# Double_H_Bridge_v1_0.net
KiCad netlist of a schematic drawn in Altium Designer
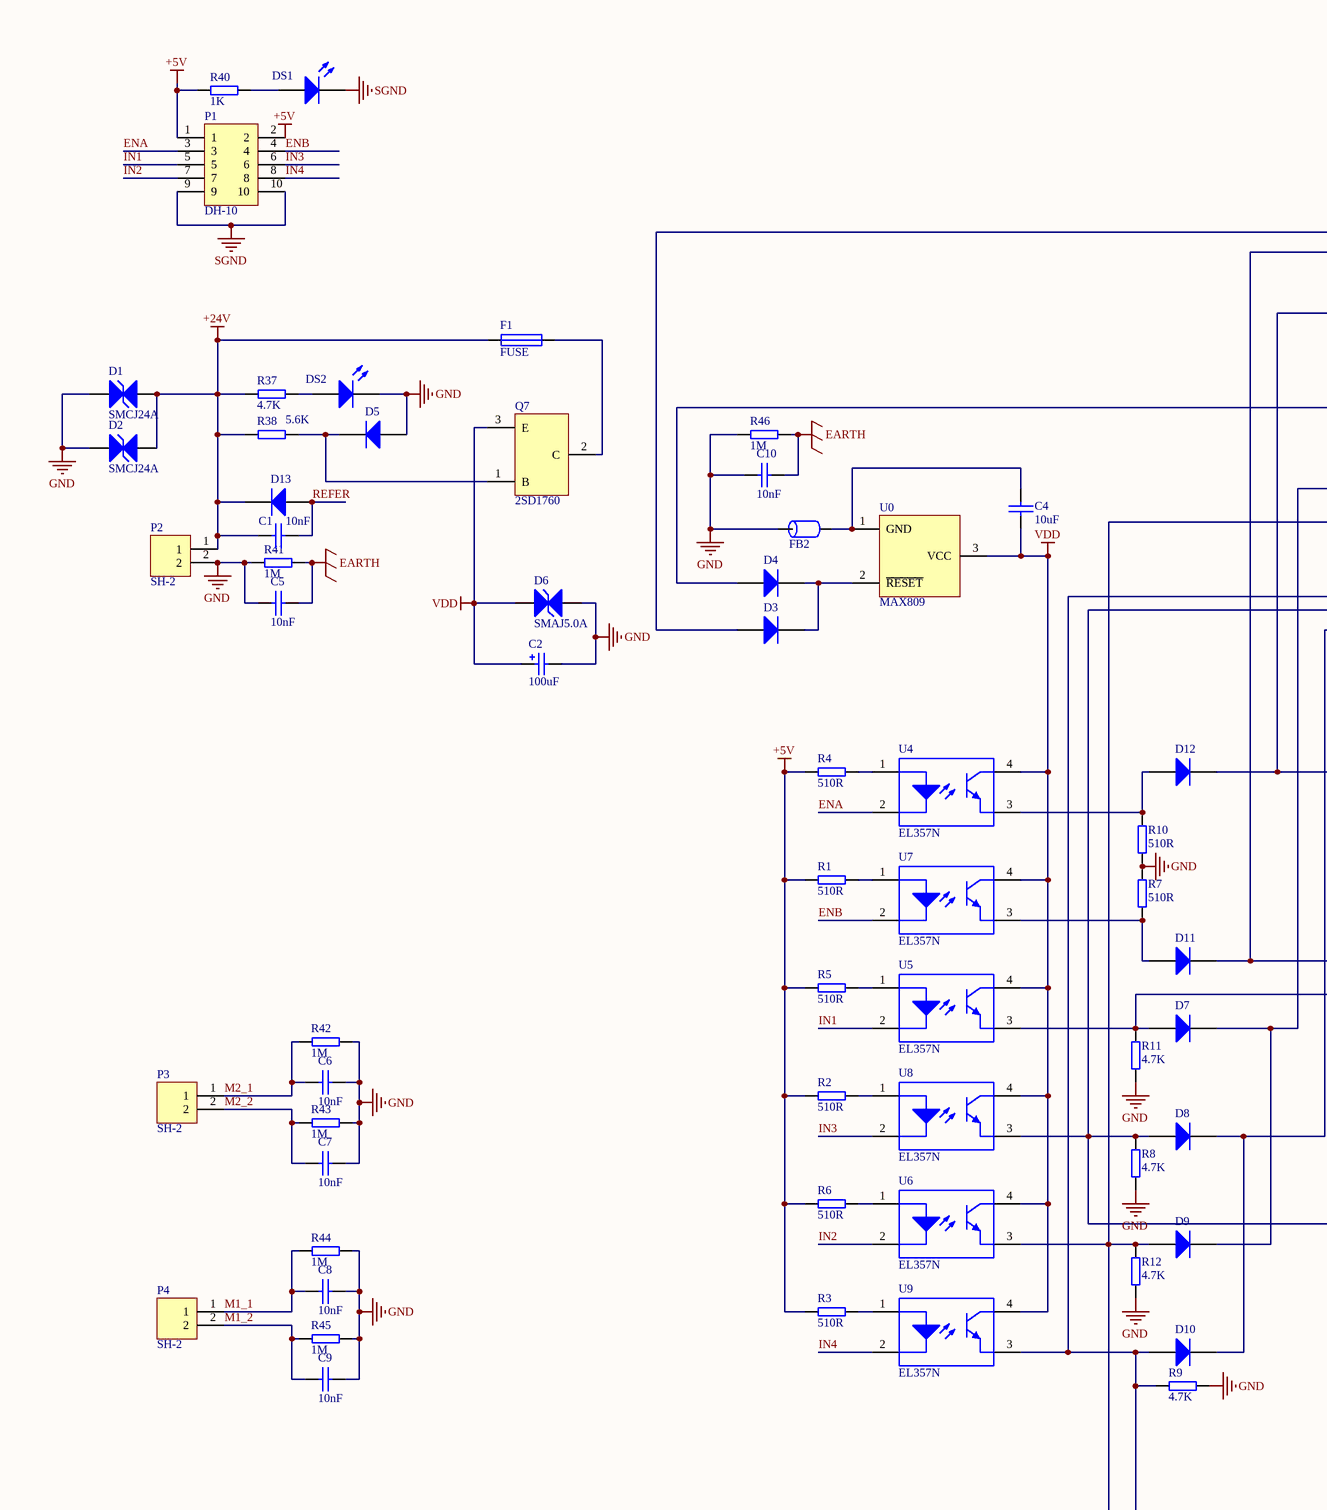
[diagram p0: Double_H_Bridge_v1.0.SchDoc, left]
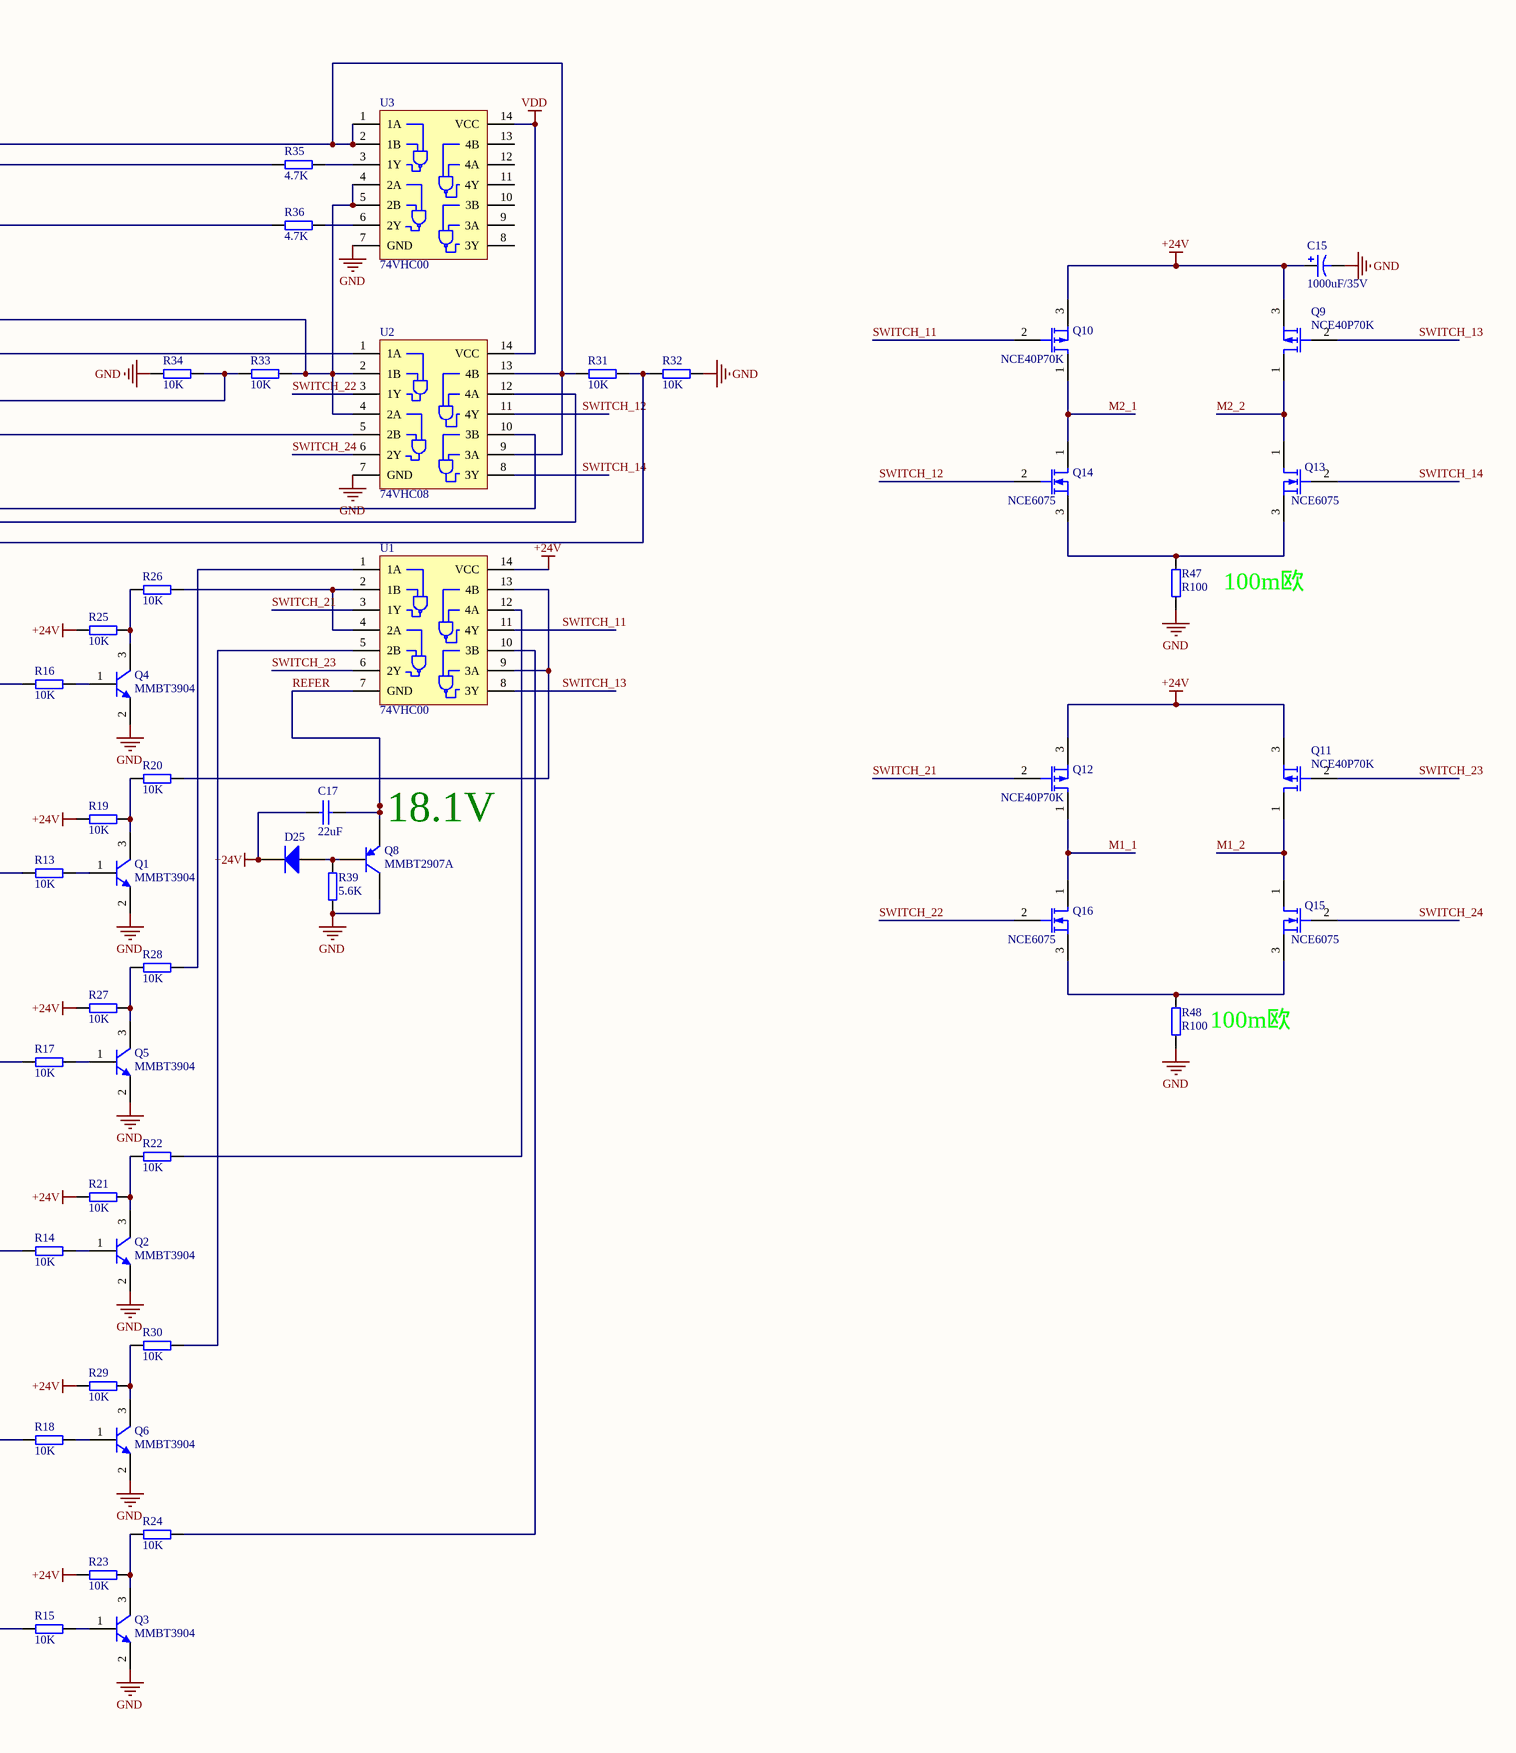
[diagram p1: Double_H_Bridge_v1.0.SchDoc, right]

(export (version "E")
  (design (tool "Eeschema 10.0.6"))
  (components
    (comp (ref "C1")
      (value "10nF")
      (footprint "0603")
      (description "电容")
      (libsource (lib "Component") (part "CAP"))
    )
    (comp (ref "C2") (value "100uF") (footprint "CA6032-C") (libsource (lib "Componet") (part "CapAEC*4")))
    (comp (ref "C4")
      (value "10uF")
      (footprint "0805")
      (description "电容")
      (libsource (lib "Component") (part "CAP"))
    )
    (comp (ref "C5")
      (value "10nF")
      (footprint "0603")
      (description "电容")
      (libsource (lib "Component") (part "CAP"))
    )
    (comp (ref "C6")
      (value "10nF")
      (footprint "0603")
      (description "电容")
      (libsource (lib "Component") (part "CAP"))
    )
    (comp (ref "C7")
      (value "10nF")
      (footprint "0603")
      (description "电容")
      (libsource (lib "Component") (part "CAP"))
    )
    (comp (ref "C8")
      (value "10nF")
      (footprint "0603")
      (description "电容")
      (libsource (lib "Component") (part "CAP"))
    )
    (comp (ref "C9")
      (value "10nF")
      (footprint "0603")
      (description "电容")
      (libsource (lib "Component") (part "CAP"))
    )
    (comp (ref "C10")
      (value "10nF")
      (footprint "0603")
      (description "电容")
      (libsource (lib "Component") (part "CAP"))
    )
    (comp (ref "C15")
      (value "1000uF/35V")
      (footprint "CAP-5mm")
      (description "Polarized Capacitor (Radial)")
      (fields (field (name "PUBLISHER") "Altium Limited"))
      (libsource (lib "Miscellaneous Devices") (part "Cap Pol1"))
    )
    (comp (ref "C17")
      (value "22uF")
      (footprint "0805")
      (description "电容")
      (libsource (lib "Component") (part "CAP"))
    )
    (comp (ref "D1")
      (value "SMCJ24A")
      (footprint "DO-214AA/SMB")
      (fields (field (name "PUBLISHER") "Altium Limited"))
      (libsource (lib "TIAN's Schlib") (part "TVS"))
    )
    (comp (ref "D2")
      (value "SMCJ24A")
      (footprint "DO-214AA/SMB")
      (fields (field (name "PUBLISHER") "Altium Limited"))
      (libsource (lib "TIAN's Schlib") (part "TVS"))
    )
    (comp (ref "D3")
      (value "1N4148")
      (footprint "DIDODE_LL-34")
      (description "Default Diode")
      (fields (field (name "PUBLISHER") "Altium Limited"))
      (libsource (lib "Miscellaneous Devices") (part "Diode"))
    )
    (comp (ref "D4")
      (value "1N4148")
      (footprint "DIDODE_LL-34")
      (description "Default Diode")
      (fields (field (name "PUBLISHER") "Altium Limited"))
      (libsource (lib "Miscellaneous Devices") (part "Diode"))
    )
    (comp (ref "D5")
      (value "1N4148")
      (footprint "DIDODE_LL-34")
      (description "Default Diode")
      (fields (field (name "PUBLISHER") "Altium Limited"))
      (libsource (lib "Miscellaneous Devices") (part "Diode"))
    )
    (comp (ref "D6")
      (value "SMAJ5.0A")
      (footprint "Diode_TP2")
      (fields (field (name "PUBLISHER") "Altium Limited"))
      (libsource (lib "TIAN's Schlib") (part "TVS"))
    )
    (comp (ref "D7")
      (value "1N4148")
      (footprint "DIDODE_LL-34")
      (description "Default Diode")
      (fields (field (name "PUBLISHER") "Altium Limited"))
      (libsource (lib "Miscellaneous Devices") (part "Diode"))
    )
    (comp (ref "D8")
      (value "1N4148")
      (footprint "DIDODE_LL-34")
      (description "Default Diode")
      (fields (field (name "PUBLISHER") "Altium Limited"))
      (libsource (lib "Miscellaneous Devices") (part "Diode"))
    )
    (comp (ref "D9")
      (value "1N4148")
      (footprint "DIDODE_LL-34")
      (description "Default Diode")
      (fields (field (name "PUBLISHER") "Altium Limited"))
      (libsource (lib "Miscellaneous Devices") (part "Diode"))
    )
    (comp (ref "D10")
      (value "1N4148")
      (footprint "DIDODE_LL-34")
      (description "Default Diode")
      (fields (field (name "PUBLISHER") "Altium Limited"))
      (libsource (lib "Miscellaneous Devices") (part "Diode"))
    )
    (comp (ref "D11")
      (value "1N4148")
      (footprint "DIDODE_LL-34")
      (description "Default Diode")
      (fields (field (name "PUBLISHER") "Altium Limited"))
      (libsource (lib "Miscellaneous Devices") (part "Diode"))
    )
    (comp (ref "D12")
      (value "1N4148")
      (footprint "DIDODE_LL-34")
      (description "Default Diode")
      (fields (field (name "PUBLISHER") "Altium Limited"))
      (libsource (lib "Miscellaneous Devices") (part "Diode"))
    )
    (comp (ref "D13")
      (value "1N4148")
      (footprint "DIDODE_LL-34")
      (description "Default Diode")
      (fields (field (name "PUBLISHER") "Altium Limited"))
      (libsource (lib "Miscellaneous Devices") (part "Diode"))
    )
    (comp (ref "D25")
      (value "1N4148")
      (footprint "DIDODE_LL-34")
      (description "Default Diode")
      (fields (field (name "PUBLISHER") "Altium Limited"))
      (libsource (lib "Miscellaneous Devices") (part "Diode"))
    )
    (comp (ref "DS1")
      (value "GREEN")
      (footprint "LED")
      (description "Typical RED, GREEN, YELLOW, AMBER GaAs LED")
      (fields (field (name "PUBLISHER") "Altium Limited"))
      (libsource (lib "Miscellaneous Devices") (part "LED2"))
    )
    (comp (ref "DS2")
      (value "GREEN")
      (footprint "LED")
      (description "Typical RED, GREEN, YELLOW, AMBER GaAs LED")
      (fields (field (name "PUBLISHER") "Altium Limited"))
      (libsource (lib "Miscellaneous Devices") (part "LED2"))
    )
    (comp (ref "F1")
      (value "FUSE")
      (footprint "1206")
      (description "保险丝")
      (libsource (lib "Component") (part "FUSE"))
    )
    (comp (ref "FB2") (value "FERRITE") (footprint "0805") (libsource (lib "Connector") (part "FERRITE")))
    (comp (ref "P1") (value "DH-10") (footprint "DH2.54-10") (libsource (lib "Connector") (part "DH-10")))
    (comp (ref "P2") (value "SH-2") (footprint "J508-2(1)") (libsource (lib "Connector") (part "SH-2")))
    (comp (ref "P3") (value "SH-2") (footprint "J508-2(1)") (libsource (lib "Connector") (part "SH-2")))
    (comp (ref "P4") (value "SH-2") (footprint "J508-2(1)") (libsource (lib "Connector") (part "SH-2")))
    (comp (ref "Q1") (value "MMBT3904") (footprint "SOT-23") (libsource (lib "Componet") (part "S8050")))
    (comp (ref "Q2") (value "MMBT3904") (footprint "SOT-23") (libsource (lib "Componet") (part "S8050")))
    (comp (ref "Q3") (value "MMBT3904") (footprint "SOT-23") (libsource (lib "Componet") (part "S8050")))
    (comp (ref "Q4") (value "MMBT3904") (footprint "SOT-23") (libsource (lib "Componet") (part "S8050")))
    (comp (ref "Q5") (value "MMBT3904") (footprint "SOT-23") (libsource (lib "Componet") (part "S8050")))
    (comp (ref "Q6") (value "MMBT3904") (footprint "SOT-23") (libsource (lib "Componet") (part "S8050")))
    (comp (ref "Q7") (value "2SD1760") (footprint "TO-252-2L") (libsource (lib "Componet") (part "2SD1760")))
    (comp (ref "Q8") (value "MMBT2907A") (footprint "901X_SOT-23") (libsource (lib "Componet") (part "PNP")))
    (comp (ref "Q9")
      (value "NCE40P70K")
      (footprint "TO-252")
      (description "P-Channel MOSFET")
      (fields (field (name "PUBLISHER") "Altium Limited"))
      (libsource (lib "Miscellaneous Devices") (part "MOSFET-P"))
    )
    (comp (ref "Q10")
      (value "NCE40P70K")
      (footprint "TO-252")
      (description "P-Channel MOSFET")
      (fields (field (name "PUBLISHER") "Altium Limited"))
      (libsource (lib "Miscellaneous Devices") (part "MOSFET-P"))
    )
    (comp (ref "Q11")
      (value "NCE40P70K")
      (footprint "TO-252")
      (description "P-Channel MOSFET")
      (fields (field (name "PUBLISHER") "Altium Limited"))
      (libsource (lib "Miscellaneous Devices") (part "MOSFET-P"))
    )
    (comp (ref "Q12")
      (value "NCE40P70K")
      (footprint "TO-252")
      (description "P-Channel MOSFET")
      (fields (field (name "PUBLISHER") "Altium Limited"))
      (libsource (lib "Miscellaneous Devices") (part "MOSFET-P"))
    )
    (comp (ref "Q13")
      (value "NCE6075")
      (footprint "TO-252")
      (description "N-Channel MOSFET")
      (fields (field (name "PUBLISHER") "Altium Limited"))
      (libsource (lib "Miscellaneous Devices") (part "MOSFET-N"))
    )
    (comp (ref "Q14")
      (value "NCE6075")
      (footprint "TO-252")
      (description "N-Channel MOSFET")
      (fields (field (name "PUBLISHER") "Altium Limited"))
      (libsource (lib "Miscellaneous Devices") (part "MOSFET-N"))
    )
    (comp (ref "Q15")
      (value "NCE6075")
      (footprint "TO-252")
      (description "N-Channel MOSFET")
      (fields (field (name "PUBLISHER") "Altium Limited"))
      (libsource (lib "Miscellaneous Devices") (part "MOSFET-N"))
    )
    (comp (ref "Q16")
      (value "NCE6075")
      (footprint "TO-252")
      (description "N-Channel MOSFET")
      (fields (field (name "PUBLISHER") "Altium Limited"))
      (libsource (lib "Miscellaneous Devices") (part "MOSFET-N"))
    )
    (comp (ref "R1")
      (value "510R")
      (footprint "0603")
      (description "电阻")
      (libsource (lib "Component") (part "RES"))
    )
    (comp (ref "R2")
      (value "510R")
      (footprint "0603")
      (description "电阻")
      (libsource (lib "Component") (part "RES"))
    )
    (comp (ref "R3")
      (value "510R")
      (footprint "0603")
      (description "电阻")
      (libsource (lib "Component") (part "RES"))
    )
    (comp (ref "R4")
      (value "510R")
      (footprint "0603")
      (description "电阻")
      (libsource (lib "Component") (part "RES"))
    )
    (comp (ref "R5")
      (value "510R")
      (footprint "0603")
      (description "电阻")
      (libsource (lib "Component") (part "RES"))
    )
    (comp (ref "R6")
      (value "510R")
      (footprint "0603")
      (description "电阻")
      (libsource (lib "Component") (part "RES"))
    )
    (comp (ref "R7")
      (value "510R")
      (footprint "0603")
      (description "电阻")
      (libsource (lib "Component") (part "RES"))
    )
    (comp (ref "R8")
      (value "4.7K")
      (footprint "0603")
      (description "电阻")
      (libsource (lib "Component") (part "RES"))
    )
    (comp (ref "R9")
      (value "4.7K")
      (footprint "0603")
      (description "电阻")
      (libsource (lib "Component") (part "RES"))
    )
    (comp (ref "R10")
      (value "510R")
      (footprint "0603")
      (description "电阻")
      (libsource (lib "Component") (part "RES"))
    )
    (comp (ref "R11")
      (value "4.7K")
      (footprint "0603")
      (description "电阻")
      (libsource (lib "Component") (part "RES"))
    )
    (comp (ref "R12")
      (value "4.7K")
      (footprint "0603")
      (description "电阻")
      (libsource (lib "Component") (part "RES"))
    )
    (comp (ref "R13")
      (value "10K")
      (footprint "0603")
      (description "电阻")
      (libsource (lib "Component") (part "RES"))
    )
    (comp (ref "R14")
      (value "10K")
      (footprint "0603")
      (description "电阻")
      (libsource (lib "Component") (part "RES"))
    )
    (comp (ref "R15")
      (value "10K")
      (footprint "0603")
      (description "电阻")
      (libsource (lib "Component") (part "RES"))
    )
    (comp (ref "R16")
      (value "10K")
      (footprint "0603")
      (description "电阻")
      (libsource (lib "Component") (part "RES"))
    )
    (comp (ref "R17")
      (value "10K")
      (footprint "0603")
      (description "电阻")
      (libsource (lib "Component") (part "RES"))
    )
    (comp (ref "R18")
      (value "10K")
      (footprint "0603")
      (description "电阻")
      (libsource (lib "Component") (part "RES"))
    )
    (comp (ref "R19")
      (value "10K")
      (footprint "0603")
      (description "电阻")
      (libsource (lib "Component") (part "RES"))
    )
    (comp (ref "R20")
      (value "10K")
      (footprint "0603")
      (description "电阻")
      (libsource (lib "Component") (part "RES"))
    )
    (comp (ref "R21")
      (value "10K")
      (footprint "0603")
      (description "电阻")
      (libsource (lib "Component") (part "RES"))
    )
    (comp (ref "R22")
      (value "10K")
      (footprint "0603")
      (description "电阻")
      (libsource (lib "Component") (part "RES"))
    )
    (comp (ref "R23")
      (value "10K")
      (footprint "0603")
      (description "电阻")
      (libsource (lib "Component") (part "RES"))
    )
    (comp (ref "R24")
      (value "10K")
      (footprint "0603")
      (description "电阻")
      (libsource (lib "Component") (part "RES"))
    )
    (comp (ref "R25")
      (value "10K")
      (footprint "0603")
      (description "电阻")
      (libsource (lib "Component") (part "RES"))
    )
    (comp (ref "R26")
      (value "10K")
      (footprint "0603")
      (description "电阻")
      (libsource (lib "Component") (part "RES"))
    )
    (comp (ref "R27")
      (value "10K")
      (footprint "0603")
      (description "电阻")
      (libsource (lib "Component") (part "RES"))
    )
    (comp (ref "R28")
      (value "10K")
      (footprint "0603")
      (description "电阻")
      (libsource (lib "Component") (part "RES"))
    )
    (comp (ref "R29")
      (value "10K")
      (footprint "0603")
      (description "电阻")
      (libsource (lib "Component") (part "RES"))
    )
    (comp (ref "R30")
      (value "10K")
      (footprint "0603")
      (description "电阻")
      (libsource (lib "Component") (part "RES"))
    )
    (comp (ref "R31")
      (value "10K")
      (footprint "0603")
      (description "电阻")
      (libsource (lib "Component") (part "RES"))
    )
    (comp (ref "R32")
      (value "10K")
      (footprint "0603")
      (description "电阻")
      (libsource (lib "Component") (part "RES"))
    )
    (comp (ref "R33")
      (value "10K")
      (footprint "0603")
      (description "电阻")
      (libsource (lib "Component") (part "RES"))
    )
    (comp (ref "R34")
      (value "10K")
      (footprint "0603")
      (description "电阻")
      (libsource (lib "Component") (part "RES"))
    )
    (comp (ref "R35")
      (value "4.7K")
      (footprint "0603")
      (description "电阻")
      (libsource (lib "Component") (part "RES"))
    )
    (comp (ref "R36")
      (value "4.7K")
      (footprint "0603")
      (description "电阻")
      (libsource (lib "Component") (part "RES"))
    )
    (comp (ref "R37")
      (value "4.7K")
      (footprint "0603")
      (description "电阻")
      (libsource (lib "Component") (part "RES"))
    )
    (comp (ref "R38")
      (value "5.6K")
      (footprint "0603")
      (description "电阻")
      (libsource (lib "Component") (part "RES"))
    )
    (comp (ref "R39")
      (value "5.6K")
      (footprint "0603")
      (description "电阻")
      (libsource (lib "Component") (part "RES"))
    )
    (comp (ref "R40")
      (value "1K")
      (footprint "0603")
      (description "电阻")
      (libsource (lib "Component") (part "RES"))
    )
    (comp (ref "R41")
      (value "1M")
      (footprint "0603")
      (description "电阻")
      (libsource (lib "Component") (part "RES"))
    )
    (comp (ref "R42")
      (value "1M")
      (footprint "0603")
      (description "电阻")
      (libsource (lib "Component") (part "RES"))
    )
    (comp (ref "R43")
      (value "1M")
      (footprint "0603")
      (description "电阻")
      (libsource (lib "Component") (part "RES"))
    )
    (comp (ref "R44")
      (value "1M")
      (footprint "0603")
      (description "电阻")
      (libsource (lib "Component") (part "RES"))
    )
    (comp (ref "R45")
      (value "1M")
      (footprint "0603")
      (description "电阻")
      (libsource (lib "Component") (part "RES"))
    )
    (comp (ref "R46")
      (value "1M")
      (footprint "0603")
      (description "电阻")
      (libsource (lib "Component") (part "RES"))
    )
    (comp (ref "R47")
      (value "R100")
      (footprint "1812")
      (description "电阻")
      (libsource (lib "Component") (part "RES"))
    )
    (comp (ref "R48")
      (value "R100")
      (footprint "1812")
      (description "电阻")
      (libsource (lib "Component") (part "RES"))
    )
    (comp (ref "U0") (value "MAX809") (footprint "SOT-23") (libsource (lib "Chip") (part "MAX809")))
    (comp (ref "U1") (value "74VHC00") (footprint "SO-14") (libsource (lib "Chip") (part "74VHC00")))
    (comp (ref "U2") (value "74VHC08") (footprint "SO-14") (libsource (lib "Chip") (part "74HC08")))
    (comp (ref "U3") (value "74VHC00") (footprint "SO-14") (libsource (lib "Chip") (part "74VHC00")))
    (comp (ref "U4") (value "EL357N") (footprint "EL357N") (libsource (lib "Componet") (part "EL357N")))
    (comp (ref "U5") (value "EL357N") (footprint "EL357N") (libsource (lib "Componet") (part "EL357N")))
    (comp (ref "U6") (value "EL357N") (footprint "EL357N") (libsource (lib "Componet") (part "EL357N")))
    (comp (ref "U7") (value "EL357N") (footprint "EL357N") (libsource (lib "Componet") (part "EL357N")))
    (comp (ref "U8") (value "EL357N") (footprint "EL357N") (libsource (lib "Componet") (part "EL357N")))
    (comp (ref "U9") (value "EL357N") (footprint "EL357N") (libsource (lib "Componet") (part "EL357N")))
  )
  (nets
    (net (code "1") (name "+5V") (class "Default")
      (node (ref "P1") (pin "1") (pinfunction "1_1") (pintype "power_in"))
      (node (ref "P1") (pin "2") (pinfunction "2_2") (pintype "power_in"))
      (node (ref "R1") (pin "1") (pinfunction "1_1") (pintype "passive"))
      (node (ref "R2") (pin "1") (pinfunction "1_1") (pintype "passive"))
      (node (ref "R3") (pin "1") (pinfunction "1_1") (pintype "passive"))
      (node (ref "R4") (pin "1") (pinfunction "1_1") (pintype "passive"))
      (node (ref "R40") (pin "1") (pinfunction "1_1") (pintype "passive"))
      (node (ref "R5") (pin "1") (pinfunction "1_1") (pintype "passive"))
      (node (ref "R6") (pin "1") (pinfunction "1_1") (pintype "passive"))
    )
    (net (code "2") (name "+24V") (class "Default")
      (node (ref "C1") (pin "1") (pinfunction "1_1") (pintype "passive"))
      (node (ref "C15") (pin "1") (pinfunction "1_1") (pintype "passive"))
      (node (ref "C17") (pin "2") (pinfunction "2_2") (pintype "passive"))
      (node (ref "D1") (pin "1") (pinfunction "A_1") (pintype "passive"))
      (node (ref "D13") (pin "2") (pinfunction "K_2") (pintype "passive"))
      (node (ref "D2") (pin "1") (pinfunction "A_1") (pintype "passive"))
      (node (ref "D25") (pin "2") (pinfunction "K_2") (pintype "passive"))
      (node (ref "F1") (pin "2") (pinfunction "2_2") (pintype "passive"))
      (node (ref "P2") (pin "1") (pinfunction "1_1") (pintype "passive"))
      (node (ref "Q10") (pin "3") (pinfunction "S_3") (pintype "passive"))
      (node (ref "Q11") (pin "3") (pinfunction "S_3") (pintype "passive"))
      (node (ref "Q12") (pin "3") (pinfunction "S_3") (pintype "passive"))
      (node (ref "Q9") (pin "3") (pinfunction "S_3") (pintype "passive"))
      (node (ref "R19") (pin "1") (pinfunction "1_1") (pintype "passive"))
      (node (ref "R21") (pin "1") (pinfunction "1_1") (pintype "passive"))
      (node (ref "R23") (pin "1") (pinfunction "1_1") (pintype "passive"))
      (node (ref "R25") (pin "1") (pinfunction "1_1") (pintype "passive"))
      (node (ref "R27") (pin "1") (pinfunction "1_1") (pintype "passive"))
      (node (ref "R29") (pin "1") (pinfunction "1_1") (pintype "passive"))
      (node (ref "R37") (pin "1") (pinfunction "1_1") (pintype "passive"))
      (node (ref "R38") (pin "1") (pinfunction "1_1") (pintype "passive"))
      (node (ref "U1") (pin "14") (pinfunction "VCC_14") (pintype "passive"))
    )
    (net (code "3") (name "/ENA") (class "Default")
      (node (ref "P1") (pin "3") (pinfunction "3_3") (pintype "power_in"))
      (node (ref "U4") (pin "2") (pinfunction "Vin-_2") (pintype "passive"))
    )
    (net (code "4") (name "/ENB") (class "Default")
      (node (ref "P1") (pin "4") (pinfunction "4_4") (pintype "power_in"))
      (node (ref "U7") (pin "2") (pinfunction "Vin-_2") (pintype "passive"))
    )
    (net (code "5") (name "/IN1") (class "Default")
      (node (ref "P1") (pin "5") (pinfunction "5_5") (pintype "power_in"))
      (node (ref "U5") (pin "2") (pinfunction "Vin-_2") (pintype "passive"))
    )
    (net (code "6") (name "/IN2") (class "Default")
      (node (ref "P1") (pin "7") (pinfunction "7_7") (pintype "power_in"))
      (node (ref "U6") (pin "2") (pinfunction "Vin-_2") (pintype "passive"))
    )
    (net (code "7") (name "/IN3") (class "Default")
      (node (ref "P1") (pin "6") (pinfunction "6_6") (pintype "power_in"))
      (node (ref "U8") (pin "2") (pinfunction "Vin-_2") (pintype "passive"))
    )
    (net (code "8") (name "/IN4") (class "Default")
      (node (ref "P1") (pin "8") (pinfunction "8_8") (pintype "power_in"))
      (node (ref "U9") (pin "2") (pinfunction "Vin-_2") (pintype "passive"))
    )
    (net (code "9") (name "/M1_1") (class "Default")
      (node (ref "C8") (pin "2") (pinfunction "2_2") (pintype "passive"))
      (node (ref "P4") (pin "1") (pinfunction "1_1") (pintype "passive"))
      (node (ref "Q12") (pin "1") (pinfunction "D_1") (pintype "passive"))
      (node (ref "Q16") (pin "1") (pinfunction "D_1") (pintype "passive"))
      (node (ref "R44") (pin "1") (pinfunction "1_1") (pintype "passive"))
    )
    (net (code "10") (name "/M1_2") (class "Default")
      (node (ref "C9") (pin "2") (pinfunction "2_2") (pintype "passive"))
      (node (ref "P4") (pin "2") (pinfunction "2_2") (pintype "passive"))
      (node (ref "Q11") (pin "1") (pinfunction "D_1") (pintype "passive"))
      (node (ref "Q15") (pin "1") (pinfunction "D_1") (pintype "passive"))
      (node (ref "R45") (pin "1") (pinfunction "1_1") (pintype "passive"))
    )
    (net (code "11") (name "/M2_1") (class "Default")
      (node (ref "C6") (pin "2") (pinfunction "2_2") (pintype "passive"))
      (node (ref "P3") (pin "1") (pinfunction "1_1") (pintype "passive"))
      (node (ref "Q10") (pin "1") (pinfunction "D_1") (pintype "passive"))
      (node (ref "Q14") (pin "1") (pinfunction "D_1") (pintype "passive"))
      (node (ref "R42") (pin "1") (pinfunction "1_1") (pintype "passive"))
    )
    (net (code "12") (name "/M2_2") (class "Default")
      (node (ref "C7") (pin "2") (pinfunction "2_2") (pintype "passive"))
      (node (ref "P3") (pin "2") (pinfunction "2_2") (pintype "passive"))
      (node (ref "Q13") (pin "1") (pinfunction "D_1") (pintype "passive"))
      (node (ref "Q9") (pin "1") (pinfunction "D_1") (pintype "passive"))
      (node (ref "R43") (pin "1") (pinfunction "1_1") (pintype "passive"))
    )
    (net (code "13") (name "/REFER") (class "Default")
      (node (ref "C1") (pin "2") (pinfunction "2_2") (pintype "passive"))
      (node (ref "C17") (pin "1") (pinfunction "1_1") (pintype "passive"))
      (node (ref "D13") (pin "1") (pinfunction "A_1") (pintype "passive"))
      (node (ref "Q8") (pin "3") (pinfunction "E_3") (pintype "passive"))
      (node (ref "U1") (pin "7") (pinfunction "GND_7") (pintype "passive"))
    )
    (net (code "14") (name "/SWITCH_11") (class "Default")
      (node (ref "Q10") (pin "2") (pinfunction "G_2") (pintype "passive"))
      (node (ref "U1") (pin "11") (pinfunction "4Y_11") (pintype "passive"))
    )
    (net (code "15") (name "/SWITCH_12") (class "Default")
      (node (ref "Q14") (pin "2") (pinfunction "G_2") (pintype "passive"))
      (node (ref "U2") (pin "11") (pinfunction "4Y_11") (pintype "passive"))
    )
    (net (code "16") (name "/SWITCH_13") (class "Default")
      (node (ref "Q9") (pin "2") (pinfunction "G_2") (pintype "passive"))
      (node (ref "U1") (pin "8") (pinfunction "3Y_8") (pintype "passive"))
    )
    (net (code "17") (name "/SWITCH_14") (class "Default")
      (node (ref "Q13") (pin "2") (pinfunction "G_2") (pintype "passive"))
      (node (ref "U2") (pin "8") (pinfunction "3Y_8") (pintype "passive"))
    )
    (net (code "18") (name "/SWITCH_21") (class "Default")
      (node (ref "Q12") (pin "2") (pinfunction "G_2") (pintype "passive"))
      (node (ref "U1") (pin "3") (pinfunction "1Y_3") (pintype "passive"))
    )
    (net (code "19") (name "/SWITCH_22") (class "Default")
      (node (ref "Q16") (pin "2") (pinfunction "G_2") (pintype "passive"))
      (node (ref "U2") (pin "3") (pinfunction "1Y_3") (pintype "passive"))
    )
    (net (code "20") (name "/SWITCH_23") (class "Default")
      (node (ref "Q11") (pin "2") (pinfunction "G_2") (pintype "passive"))
      (node (ref "U1") (pin "6") (pinfunction "2Y_6") (pintype "passive"))
    )
    (net (code "21") (name "/SWITCH_24") (class "Default")
      (node (ref "Q15") (pin "2") (pinfunction "G_2") (pintype "passive"))
      (node (ref "U2") (pin "6") (pinfunction "2Y_6") (pintype "passive"))
    )
    (net (code "22") (name "EARTH") (class "Default")
      (node (ref "C10") (pin "1") (pinfunction "1_1") (pintype "passive"))
      (node (ref "C5") (pin "1") (pinfunction "1_1") (pintype "passive"))
      (node (ref "R41") (pin "2") (pinfunction "2_2") (pintype "passive"))
      (node (ref "R46") (pin "2") (pinfunction "2_2") (pintype "passive"))
    )
    (net (code "23") (name "GND") (class "Default")
      (node (ref "C10") (pin "2") (pinfunction "2_2") (pintype "passive"))
      (node (ref "C15") (pin "2") (pinfunction "2_2") (pintype "passive"))
      (node (ref "C2") (pin "2") (pinfunction "2_2") (pintype "passive"))
      (node (ref "C5") (pin "2") (pinfunction "2_2") (pintype "passive"))
      (node (ref "C6") (pin "1") (pinfunction "1_1") (pintype "passive"))
      (node (ref "C7") (pin "1") (pinfunction "1_1") (pintype "passive"))
      (node (ref "C8") (pin "1") (pinfunction "1_1") (pintype "passive"))
      (node (ref "C9") (pin "1") (pinfunction "1_1") (pintype "passive"))
      (node (ref "D1") (pin "2") (pinfunction "K_2") (pintype "passive"))
      (node (ref "D2") (pin "2") (pinfunction "K_2") (pintype "passive"))
      (node (ref "D5") (pin "1") (pinfunction "A_1") (pintype "passive"))
      (node (ref "D6") (pin "1") (pinfunction "A_1") (pintype "passive"))
      (node (ref "DS2") (pin "2") (pinfunction "K_2") (pintype "passive"))
      (node (ref "FB2") (pin "2") (pinfunction "2_2") (pintype "passive"))
      (node (ref "P2") (pin "2") (pinfunction "2_2") (pintype "passive"))
      (node (ref "Q1") (pin "2") (pinfunction "E_2") (pintype "passive"))
      (node (ref "Q2") (pin "2") (pinfunction "E_2") (pintype "passive"))
      (node (ref "Q3") (pin "2") (pinfunction "E_2") (pintype "passive"))
      (node (ref "Q4") (pin "2") (pinfunction "E_2") (pintype "passive"))
      (node (ref "Q5") (pin "2") (pinfunction "E_2") (pintype "passive"))
      (node (ref "Q6") (pin "2") (pinfunction "E_2") (pintype "passive"))
      (node (ref "Q8") (pin "1") (pinfunction "C_1") (pintype "passive"))
      (node (ref "R10") (pin "1") (pinfunction "1_1") (pintype "passive"))
      (node (ref "R11") (pin "1") (pinfunction "1_1") (pintype "passive"))
      (node (ref "R12") (pin "1") (pinfunction "1_1") (pintype "passive"))
      (node (ref "R32") (pin "2") (pinfunction "2_2") (pintype "passive"))
      (node (ref "R34") (pin "1") (pinfunction "1_1") (pintype "passive"))
      (node (ref "R39") (pin "1") (pinfunction "1_1") (pintype "passive"))
      (node (ref "R41") (pin "1") (pinfunction "1_1") (pintype "passive"))
      (node (ref "R42") (pin "2") (pinfunction "2_2") (pintype "passive"))
      (node (ref "R43") (pin "2") (pinfunction "2_2") (pintype "passive"))
      (node (ref "R44") (pin "2") (pinfunction "2_2") (pintype "passive"))
      (node (ref "R45") (pin "2") (pinfunction "2_2") (pintype "passive"))
      (node (ref "R46") (pin "1") (pinfunction "1_1") (pintype "passive"))
      (node (ref "R47") (pin "1") (pinfunction "1_1") (pintype "passive"))
      (node (ref "R48") (pin "1") (pinfunction "1_1") (pintype "passive"))
      (node (ref "R7") (pin "2") (pinfunction "2_2") (pintype "passive"))
      (node (ref "R8") (pin "1") (pinfunction "1_1") (pintype "passive"))
      (node (ref "R9") (pin "2") (pinfunction "2_2") (pintype "passive"))
      (node (ref "U2") (pin "7") (pinfunction "GND_7") (pintype "passive"))
      (node (ref "U3") (pin "7") (pinfunction "GND_7") (pintype "passive"))
    )
    (net (code "24") (name "Net-(D3-A)") (class "Default")
      (node (ref "D3") (pin "1") (pinfunction "A_1") (pintype "passive"))
      (node (ref "R31") (pin "1") (pinfunction "1_1") (pintype "passive"))
      (node (ref "U2") (pin "13") (pinfunction "4B_13") (pintype "passive"))
      (node (ref "U2") (pin "9") (pinfunction "3A_9") (pintype "passive"))
      (node (ref "U3") (pin "1") (pinfunction "1A_1") (pintype "passive"))
      (node (ref "U3") (pin "2") (pinfunction "1B_2") (pintype "passive"))
    )
    (net (code "25") (name "Net-(D3-K)") (class "Default")
      (node (ref "D3") (pin "2") (pinfunction "K_2") (pintype "passive"))
      (node (ref "D4") (pin "2") (pinfunction "K_2") (pintype "passive"))
      (node (ref "U0") (pin "2") (pinfunction "~{RESET}_2") (pintype "passive"))
    )
    (net (code "26") (name "Net-(D4-A)") (class "Default")
      (node (ref "D4") (pin "1") (pinfunction "A_1") (pintype "passive"))
      (node (ref "R33") (pin "2") (pinfunction "2_2") (pintype "passive"))
      (node (ref "U2") (pin "2") (pinfunction "1B_2") (pintype "passive"))
      (node (ref "U2") (pin "4") (pinfunction "2A_4") (pintype "passive"))
      (node (ref "U3") (pin "4") (pinfunction "2A_4") (pintype "passive"))
      (node (ref "U3") (pin "5") (pinfunction "2B_5") (pintype "passive"))
    )
    (net (code "27") (name "Net-(D5-K)") (class "Default")
      (node (ref "D5") (pin "2") (pinfunction "K_2") (pintype "passive"))
      (node (ref "Q7") (pin "1") (pinfunction "B_1") (pintype "passive"))
      (node (ref "R38") (pin "2") (pinfunction "2_2") (pintype "passive"))
    )
    (net (code "28") (name "Net-(D7-A)") (class "Default")
      (node (ref "D7") (pin "1") (pinfunction "A_1") (pintype "passive"))
      (node (ref "R11") (pin "2") (pinfunction "2_2") (pintype "passive"))
      (node (ref "R17") (pin "1") (pinfunction "1_1") (pintype "passive"))
      (node (ref "U2") (pin "1") (pinfunction "1A_1") (pintype "passive"))
      (node (ref "U5") (pin "3") (pinfunction "E_3") (pintype "passive"))
    )
    (net (code "29") (name "Net-(D7-K)") (class "Default")
      (node (ref "D7") (pin "2") (pinfunction "K_2") (pintype "passive"))
      (node (ref "D9") (pin "2") (pinfunction "K_2") (pintype "passive"))
      (node (ref "R33") (pin "1") (pinfunction "1_1") (pintype "passive"))
      (node (ref "R34") (pin "2") (pinfunction "2_2") (pintype "passive"))
    )
    (net (code "30") (name "Net-(D8-A)") (class "Default")
      (node (ref "D8") (pin "1") (pinfunction "A_1") (pintype "passive"))
      (node (ref "R14") (pin "1") (pinfunction "1_1") (pintype "passive"))
      (node (ref "R8") (pin "2") (pinfunction "2_2") (pintype "passive"))
      (node (ref "U2") (pin "12") (pinfunction "4A_12") (pintype "passive"))
      (node (ref "U8") (pin "3") (pinfunction "E_3") (pintype "passive"))
    )
    (net (code "31") (name "Net-(D9-A)") (class "Default")
      (node (ref "D9") (pin "1") (pinfunction "A_1") (pintype "passive"))
      (node (ref "R12") (pin "2") (pinfunction "2_2") (pintype "passive"))
      (node (ref "R18") (pin "1") (pinfunction "1_1") (pintype "passive"))
      (node (ref "U2") (pin "5") (pinfunction "2B_5") (pintype "passive"))
      (node (ref "U6") (pin "3") (pinfunction "E_3") (pintype "passive"))
    )
    (net (code "32") (name "Net-(D10-A)") (class "Default")
      (node (ref "D10") (pin "1") (pinfunction "A_1") (pintype "passive"))
      (node (ref "R15") (pin "1") (pinfunction "1_1") (pintype "passive"))
      (node (ref "R9") (pin "1") (pinfunction "1_1") (pintype "passive"))
      (node (ref "U2") (pin "10") (pinfunction "3B_10") (pintype "passive"))
      (node (ref "U9") (pin "3") (pinfunction "E_3") (pintype "passive"))
    )
    (net (code "33") (name "Net-(D10-K)") (class "Default")
      (node (ref "D10") (pin "2") (pinfunction "K_2") (pintype "passive"))
      (node (ref "D8") (pin "2") (pinfunction "K_2") (pintype "passive"))
      (node (ref "R31") (pin "2") (pinfunction "2_2") (pintype "passive"))
      (node (ref "R32") (pin "1") (pinfunction "1_1") (pintype "passive"))
    )
    (net (code "34") (name "Net-(D11-A)") (class "Default")
      (node (ref "D11") (pin "1") (pinfunction "A_1") (pintype "passive"))
      (node (ref "R7") (pin "1") (pinfunction "1_1") (pintype "passive"))
      (node (ref "U7") (pin "3") (pinfunction "E_3") (pintype "passive"))
    )
    (net (code "35") (name "Net-(D11-K)") (class "Default")
      (node (ref "D11") (pin "2") (pinfunction "K_2") (pintype "passive"))
      (node (ref "R13") (pin "1") (pinfunction "1_1") (pintype "passive"))
      (node (ref "R35") (pin "1") (pinfunction "1_1") (pintype "passive"))
    )
    (net (code "36") (name "Net-(D12-A)") (class "Default")
      (node (ref "D12") (pin "1") (pinfunction "A_1") (pintype "passive"))
      (node (ref "R10") (pin "2") (pinfunction "2_2") (pintype "passive"))
      (node (ref "U4") (pin "3") (pinfunction "E_3") (pintype "passive"))
    )
    (net (code "37") (name "Net-(D12-K)") (class "Default")
      (node (ref "D12") (pin "2") (pinfunction "K_2") (pintype "passive"))
      (node (ref "R16") (pin "1") (pinfunction "1_1") (pintype "passive"))
      (node (ref "R36") (pin "1") (pinfunction "1_1") (pintype "passive"))
    )
    (net (code "38") (name "Net-(D25-A)") (class "Default")
      (node (ref "D25") (pin "1") (pinfunction "A_1") (pintype "passive"))
      (node (ref "Q8") (pin "2") (pinfunction "B_2") (pintype "passive"))
      (node (ref "R39") (pin "2") (pinfunction "2_2") (pintype "passive"))
    )
    (net (code "39") (name "Net-(DS1-A)") (class "Default")
      (node (ref "DS1") (pin "1") (pinfunction "A_1") (pintype "passive"))
      (node (ref "R40") (pin "2") (pinfunction "2_2") (pintype "passive"))
    )
    (net (code "40") (name "Net-(DS2-A)") (class "Default")
      (node (ref "DS2") (pin "1") (pinfunction "A_1") (pintype "passive"))
      (node (ref "R37") (pin "2") (pinfunction "2_2") (pintype "passive"))
    )
    (net (code "41") (name "Net-(Q1-B)") (class "Default")
      (node (ref "Q1") (pin "1") (pinfunction "B_1") (pintype "passive"))
      (node (ref "R13") (pin "2") (pinfunction "2_2") (pintype "passive"))
    )
    (net (code "42") (name "Net-(Q1-C)") (class "Default")
      (node (ref "Q1") (pin "3") (pinfunction "C_3") (pintype "passive"))
      (node (ref "R19") (pin "2") (pinfunction "2_2") (pintype "passive"))
      (node (ref "R20") (pin "1") (pinfunction "1_1") (pintype "passive"))
    )
    (net (code "43") (name "Net-(Q2-B)") (class "Default")
      (node (ref "Q2") (pin "1") (pinfunction "B_1") (pintype "passive"))
      (node (ref "R14") (pin "2") (pinfunction "2_2") (pintype "passive"))
    )
    (net (code "44") (name "Net-(Q2-C)") (class "Default")
      (node (ref "Q2") (pin "3") (pinfunction "C_3") (pintype "passive"))
      (node (ref "R21") (pin "2") (pinfunction "2_2") (pintype "passive"))
      (node (ref "R22") (pin "1") (pinfunction "1_1") (pintype "passive"))
    )
    (net (code "45") (name "Net-(Q3-B)") (class "Default")
      (node (ref "Q3") (pin "1") (pinfunction "B_1") (pintype "passive"))
      (node (ref "R15") (pin "2") (pinfunction "2_2") (pintype "passive"))
    )
    (net (code "46") (name "Net-(Q3-C)") (class "Default")
      (node (ref "Q3") (pin "3") (pinfunction "C_3") (pintype "passive"))
      (node (ref "R23") (pin "2") (pinfunction "2_2") (pintype "passive"))
      (node (ref "R24") (pin "1") (pinfunction "1_1") (pintype "passive"))
    )
    (net (code "47") (name "Net-(Q4-B)") (class "Default")
      (node (ref "Q4") (pin "1") (pinfunction "B_1") (pintype "passive"))
      (node (ref "R16") (pin "2") (pinfunction "2_2") (pintype "passive"))
    )
    (net (code "48") (name "Net-(Q4-C)") (class "Default")
      (node (ref "Q4") (pin "3") (pinfunction "C_3") (pintype "passive"))
      (node (ref "R25") (pin "2") (pinfunction "2_2") (pintype "passive"))
      (node (ref "R26") (pin "1") (pinfunction "1_1") (pintype "passive"))
    )
    (net (code "49") (name "Net-(Q5-B)") (class "Default")
      (node (ref "Q5") (pin "1") (pinfunction "B_1") (pintype "passive"))
      (node (ref "R17") (pin "2") (pinfunction "2_2") (pintype "passive"))
    )
    (net (code "50") (name "Net-(Q5-C)") (class "Default")
      (node (ref "Q5") (pin "3") (pinfunction "C_3") (pintype "passive"))
      (node (ref "R27") (pin "2") (pinfunction "2_2") (pintype "passive"))
      (node (ref "R28") (pin "1") (pinfunction "1_1") (pintype "passive"))
    )
    (net (code "51") (name "Net-(Q6-B)") (class "Default")
      (node (ref "Q6") (pin "1") (pinfunction "B_1") (pintype "passive"))
      (node (ref "R18") (pin "2") (pinfunction "2_2") (pintype "passive"))
    )
    (net (code "52") (name "Net-(Q6-C)") (class "Default")
      (node (ref "Q6") (pin "3") (pinfunction "C_3") (pintype "passive"))
      (node (ref "R29") (pin "2") (pinfunction "2_2") (pintype "passive"))
      (node (ref "R30") (pin "1") (pinfunction "1_1") (pintype "passive"))
    )
    (net (code "53") (name "Net-(Q7-C)") (class "Default")
      (node (ref "F1") (pin "1") (pinfunction "1_1") (pintype "passive"))
      (node (ref "Q7") (pin "2") (pinfunction "C_2") (pintype "passive"))
    )
    (net (code "54") (name "Net-(Q13-S)") (class "Default")
      (node (ref "Q13") (pin "3") (pinfunction "S_3") (pintype "passive"))
      (node (ref "Q14") (pin "3") (pinfunction "S_3") (pintype "passive"))
      (node (ref "R47") (pin "2") (pinfunction "2_2") (pintype "passive"))
    )
    (net (code "55") (name "Net-(Q15-S)") (class "Default")
      (node (ref "Q15") (pin "3") (pinfunction "S_3") (pintype "passive"))
      (node (ref "Q16") (pin "3") (pinfunction "S_3") (pintype "passive"))
      (node (ref "R48") (pin "2") (pinfunction "2_2") (pintype "passive"))
    )
    (net (code "56") (name "Net-(U0-GND)") (class "Default")
      (node (ref "C4") (pin "2") (pinfunction "2_2") (pintype "passive"))
      (node (ref "FB2") (pin "1") (pinfunction "1_1") (pintype "passive"))
      (node (ref "U0") (pin "1") (pinfunction "GND_1") (pintype "passive"))
    )
    (net (code "57") (name "Net-(U1-1A)") (class "Default")
      (node (ref "R28") (pin "2") (pinfunction "2_2") (pintype "passive"))
      (node (ref "U1") (pin "1") (pinfunction "1A_1") (pintype "passive"))
    )
    (net (code "58") (name "Net-(U1-1B)") (class "Default")
      (node (ref "R26") (pin "2") (pinfunction "2_2") (pintype "passive"))
      (node (ref "U1") (pin "2") (pinfunction "1B_2") (pintype "passive"))
      (node (ref "U1") (pin "4") (pinfunction "2A_4") (pintype "passive"))
    )
    (net (code "59") (name "Net-(U1-2B)") (class "Default")
      (node (ref "R30") (pin "2") (pinfunction "2_2") (pintype "passive"))
      (node (ref "U1") (pin "5") (pinfunction "2B_5") (pintype "passive"))
    )
    (net (code "60") (name "Net-(U1-3A)") (class "Default")
      (node (ref "R20") (pin "2") (pinfunction "2_2") (pintype "passive"))
      (node (ref "U1") (pin "13") (pinfunction "4B_13") (pintype "passive"))
      (node (ref "U1") (pin "9") (pinfunction "3A_9") (pintype "passive"))
    )
    (net (code "61") (name "Net-(U1-3B)") (class "Default")
      (node (ref "R24") (pin "2") (pinfunction "2_2") (pintype "passive"))
      (node (ref "U1") (pin "10") (pinfunction "3B_10") (pintype "passive"))
    )
    (net (code "62") (name "Net-(U1-4A)") (class "Default")
      (node (ref "R22") (pin "2") (pinfunction "2_2") (pintype "passive"))
      (node (ref "U1") (pin "12") (pinfunction "4A_12") (pintype "passive"))
    )
    (net (code "63") (name "Net-(U3-1Y)") (class "Default")
      (node (ref "R35") (pin "2") (pinfunction "2_2") (pintype "passive"))
      (node (ref "U3") (pin "3") (pinfunction "1Y_3") (pintype "passive"))
    )
    (net (code "64") (name "Net-(U3-2Y)") (class "Default")
      (node (ref "R36") (pin "2") (pinfunction "2_2") (pintype "passive"))
      (node (ref "U3") (pin "6") (pinfunction "2Y_6") (pintype "passive"))
    )
    (net (code "65") (name "Net-(U4-Vin+)") (class "Default")
      (node (ref "R4") (pin "2") (pinfunction "2_2") (pintype "passive"))
      (node (ref "U4") (pin "1") (pinfunction "Vin+_1") (pintype "passive"))
    )
    (net (code "66") (name "Net-(U5-Vin+)") (class "Default")
      (node (ref "R5") (pin "2") (pinfunction "2_2") (pintype "passive"))
      (node (ref "U5") (pin "1") (pinfunction "Vin+_1") (pintype "passive"))
    )
    (net (code "67") (name "Net-(U6-Vin+)") (class "Default")
      (node (ref "R6") (pin "2") (pinfunction "2_2") (pintype "passive"))
      (node (ref "U6") (pin "1") (pinfunction "Vin+_1") (pintype "passive"))
    )
    (net (code "68") (name "Net-(U7-Vin+)") (class "Default")
      (node (ref "R1") (pin "2") (pinfunction "2_2") (pintype "passive"))
      (node (ref "U7") (pin "1") (pinfunction "Vin+_1") (pintype "passive"))
    )
    (net (code "69") (name "Net-(U8-Vin+)") (class "Default")
      (node (ref "R2") (pin "2") (pinfunction "2_2") (pintype "passive"))
      (node (ref "U8") (pin "1") (pinfunction "Vin+_1") (pintype "passive"))
    )
    (net (code "70") (name "Net-(U9-Vin+)") (class "Default")
      (node (ref "R3") (pin "2") (pinfunction "2_2") (pintype "passive"))
      (node (ref "U9") (pin "1") (pinfunction "Vin+_1") (pintype "passive"))
    )
    (net (code "71") (name "SGND") (class "Default")
      (node (ref "DS1") (pin "2") (pinfunction "K_2") (pintype "passive"))
      (node (ref "P1") (pin "10") (pinfunction "10_10") (pintype "power_in"))
      (node (ref "P1") (pin "9") (pinfunction "9_9") (pintype "power_in"))
    )
    (net (code "72") (name "VDD") (class "Default")
      (node (ref "C2") (pin "1") (pinfunction "1_1") (pintype "passive"))
      (node (ref "C4") (pin "1") (pinfunction "1_1") (pintype "passive"))
      (node (ref "D6") (pin "2") (pinfunction "K_2") (pintype "passive"))
      (node (ref "Q7") (pin "3") (pinfunction "E_3") (pintype "passive"))
      (node (ref "U0") (pin "3") (pinfunction "VCC_3") (pintype "passive"))
      (node (ref "U2") (pin "14") (pinfunction "VCC_14") (pintype "passive"))
      (node (ref "U3") (pin "14") (pinfunction "VCC_14") (pintype "passive"))
      (node (ref "U4") (pin "4") (pinfunction "C_4") (pintype "passive"))
      (node (ref "U5") (pin "4") (pinfunction "C_4") (pintype "passive"))
      (node (ref "U6") (pin "4") (pinfunction "C_4") (pintype "passive"))
      (node (ref "U7") (pin "4") (pinfunction "C_4") (pintype "passive"))
      (node (ref "U8") (pin "4") (pinfunction "C_4") (pintype "passive"))
      (node (ref "U9") (pin "4") (pinfunction "C_4") (pintype "passive"))
    )
    (net (code "73") (name "unconnected-(U3-3A-Pad9)") (class "Default")
      (node (ref "U3") (pin "9") (pinfunction "3A_9") (pintype "passive"))
    )
    (net (code "74") (name "unconnected-(U3-3B-Pad10)") (class "Default")
      (node (ref "U3") (pin "10") (pinfunction "3B_10") (pintype "passive"))
    )
    (net (code "75") (name "unconnected-(U3-3Y-Pad8)") (class "Default")
      (node (ref "U3") (pin "8") (pinfunction "3Y_8") (pintype "passive"))
    )
    (net (code "76") (name "unconnected-(U3-4A-Pad12)") (class "Default")
      (node (ref "U3") (pin "12") (pinfunction "4A_12") (pintype "passive"))
    )
    (net (code "77") (name "unconnected-(U3-4B-Pad13)") (class "Default")
      (node (ref "U3") (pin "13") (pinfunction "4B_13") (pintype "passive"))
    )
    (net (code "78") (name "unconnected-(U3-4Y-Pad11)") (class "Default")
      (node (ref "U3") (pin "11") (pinfunction "4Y_11") (pintype "passive"))
    )
  )
)
